# octacore.net
KiCad netlist of a schematic drawn in EAGLE
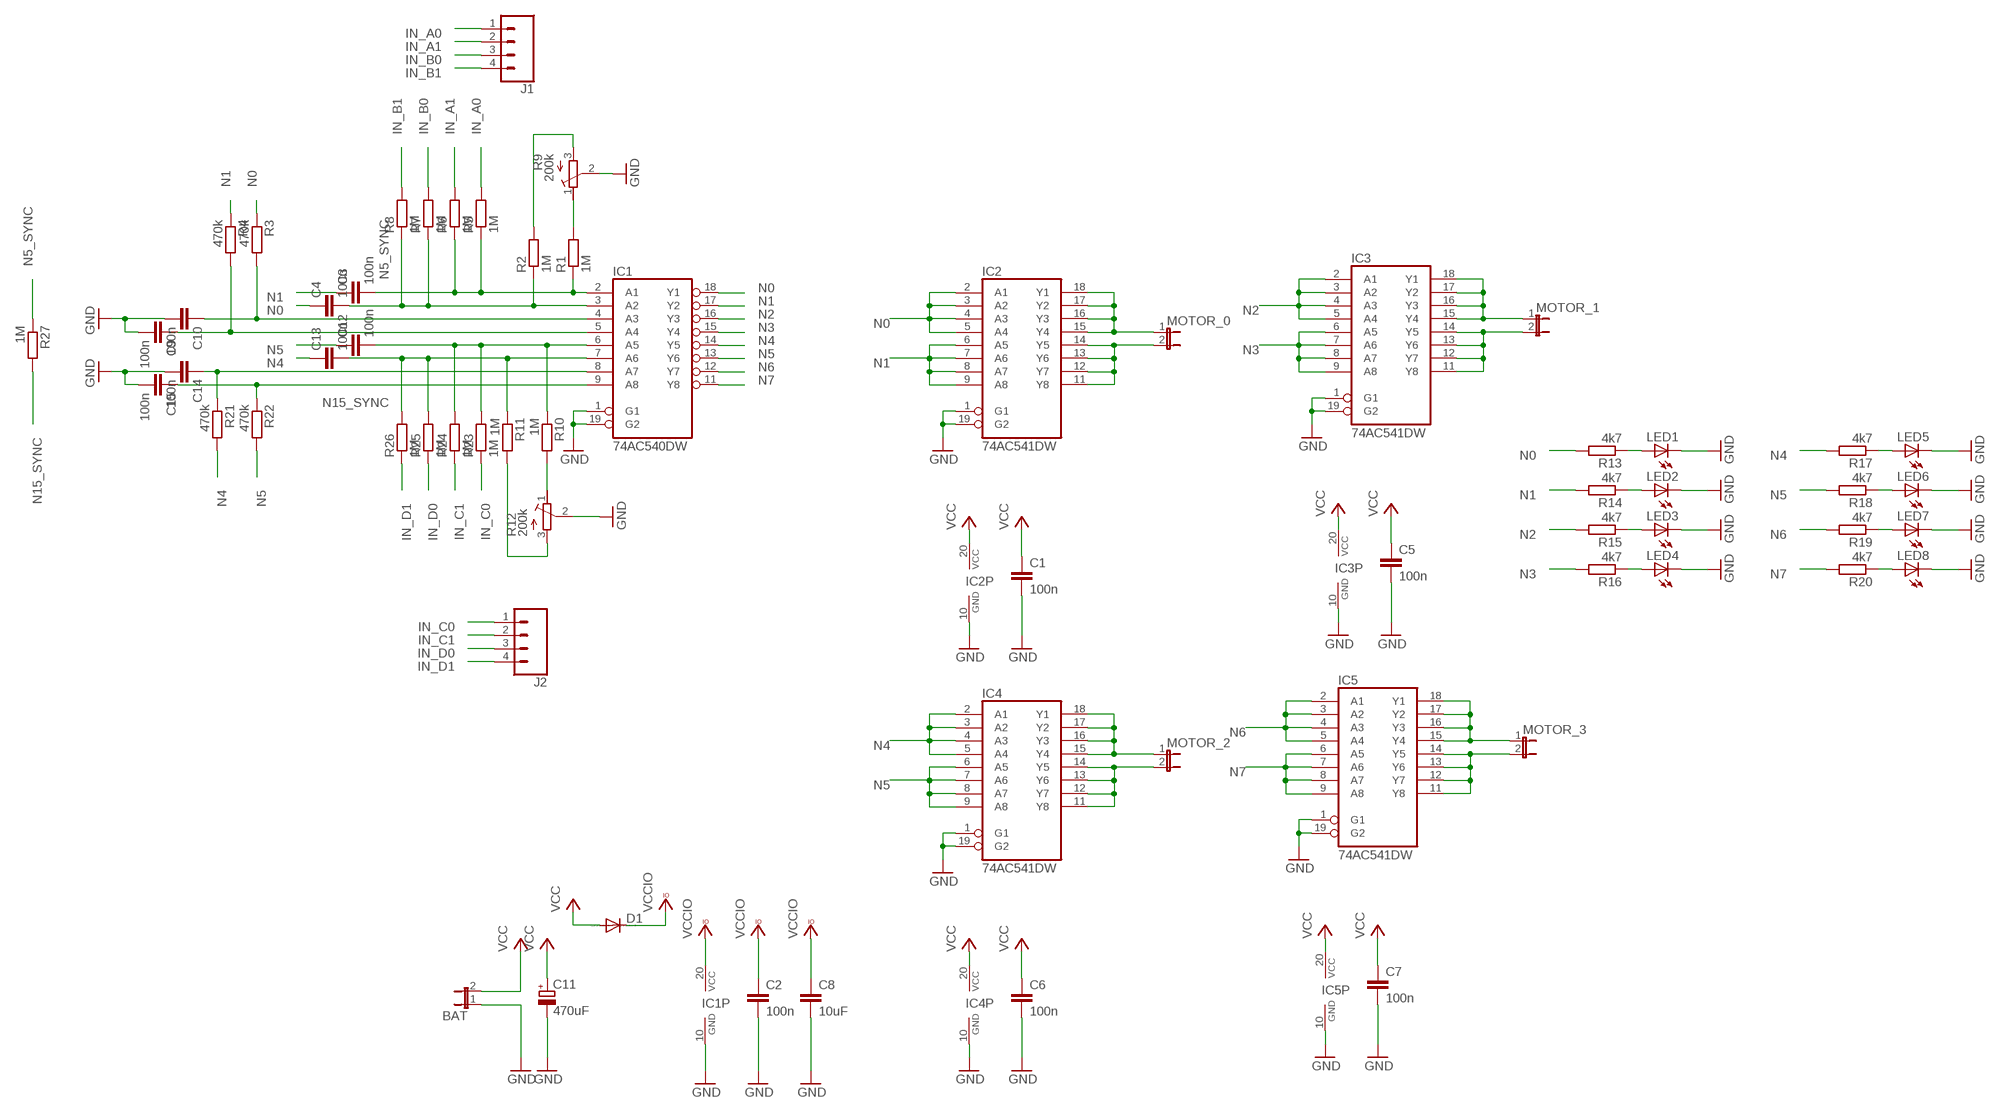
[diagram p0: schematic, sheet 1]

(export (version "E")
  (design (tool "Eeschema 10.0.6"))
  (components
    (comp (ref "BAT")
      (value "JUMPER_JP1E")
      (footprint "eagle-import:JUMPER_JP1")
      (libsource (lib "eagle-import") (part "JUMPER_JP1E"))
    )
    (comp (ref "C1")
      (value "100n")
      (footprint "eagle-import:C0805")
      (libsource (lib "eagle-import") (part "C-EUC0805"))
    )
    (comp (ref "C2")
      (value "100n")
      (footprint "eagle-import:C0805")
      (libsource (lib "eagle-import") (part "C-EUC0805"))
    )
    (comp (ref "C3")
      (value "100n")
      (footprint "eagle-import:C0805")
      (libsource (lib "eagle-import") (part "C-EUC0805"))
    )
    (comp (ref "C4")
      (value "100n")
      (footprint "eagle-import:C0805")
      (libsource (lib "eagle-import") (part "C-EUC0805"))
    )
    (comp (ref "C5")
      (value "100n")
      (footprint "eagle-import:C0805")
      (libsource (lib "eagle-import") (part "C-EUC0805"))
    )
    (comp (ref "C6")
      (value "100n")
      (footprint "eagle-import:C0805")
      (libsource (lib "eagle-import") (part "C-EUC0805"))
    )
    (comp (ref "C7")
      (value "100n")
      (footprint "eagle-import:C0805")
      (libsource (lib "eagle-import") (part "C-EUC0805"))
    )
    (comp (ref "C8")
      (value "10uF")
      (footprint "eagle-import:C0805")
      (libsource (lib "eagle-import") (part "C-EUC0805"))
    )
    (comp (ref "C9")
      (value "100n")
      (footprint "eagle-import:C0805")
      (libsource (lib "eagle-import") (part "C-EUC0805"))
    )
    (comp (ref "C10")
      (value "100n")
      (footprint "eagle-import:C0805")
      (libsource (lib "eagle-import") (part "C-EUC0805"))
    )
    (comp (ref "C11")
      (value "470uF")
      (footprint "eagle-import:140CLH-1010")
      (libsource (lib "eagle-import") (part "CPOL-EU140CLH-1010"))
    )
    (comp (ref "C12")
      (value "100n")
      (footprint "eagle-import:C0805")
      (libsource (lib "eagle-import") (part "C-EUC0805"))
    )
    (comp (ref "C13")
      (value "100n")
      (footprint "eagle-import:C0805")
      (libsource (lib "eagle-import") (part "C-EUC0805"))
    )
    (comp (ref "C14")
      (value "100n")
      (footprint "eagle-import:C0805")
      (libsource (lib "eagle-import") (part "C-EUC0805"))
    )
    (comp (ref "C15")
      (value "100n")
      (footprint "eagle-import:C0805")
      (libsource (lib "eagle-import") (part "C-EUC0805"))
    )
    (comp (ref "D1")
      (value "DIODE-DO214AA")
      (footprint "eagle-import:DO214AA")
      (libsource (lib "eagle-import") (part "DIODE-DO214AA"))
    )
    (comp (ref "IC1")
      (value "74AC540DW")
      (footprint "eagle-import:SO20W")
      (libsource (lib "eagle-import") (part "74540DWAC"))
    )
    (comp (ref "IC2")
      (value "74AC541DW")
      (footprint "eagle-import:SO20W")
      (libsource (lib "eagle-import") (part "74541DWAC"))
    )
    (comp (ref "IC3")
      (value "74AC541DW")
      (footprint "eagle-import:SO20W")
      (libsource (lib "eagle-import") (part "74541DWAC"))
    )
    (comp (ref "IC4")
      (value "74AC541DW")
      (footprint "eagle-import:SO20W")
      (libsource (lib "eagle-import") (part "74541DWAC"))
    )
    (comp (ref "IC5")
      (value "74AC541DW")
      (footprint "eagle-import:SO20W")
      (libsource (lib "eagle-import") (part "74541DWAC"))
    )
    (comp (ref "J1")
      (value "CONN_04")
      (footprint "eagle-import:1X04")
      (libsource (lib "eagle-import") (part "CONN_04"))
    )
    (comp (ref "J2")
      (value "CONN_04")
      (footprint "eagle-import:1X04")
      (libsource (lib "eagle-import") (part "CONN_04"))
    )
    (comp (ref "LED1")
      (value "LEDSML1206")
      (footprint "eagle-import:SML1206")
      (libsource (lib "eagle-import") (part "LEDSML1206"))
    )
    (comp (ref "LED2")
      (value "LEDSML1206")
      (footprint "eagle-import:SML1206")
      (libsource (lib "eagle-import") (part "LEDSML1206"))
    )
    (comp (ref "LED3")
      (value "LEDSML1206")
      (footprint "eagle-import:SML1206")
      (libsource (lib "eagle-import") (part "LEDSML1206"))
    )
    (comp (ref "LED4")
      (value "LEDSML1206")
      (footprint "eagle-import:SML1206")
      (libsource (lib "eagle-import") (part "LEDSML1206"))
    )
    (comp (ref "LED5")
      (value "LEDSML1206")
      (footprint "eagle-import:SML1206")
      (libsource (lib "eagle-import") (part "LEDSML1206"))
    )
    (comp (ref "LED6")
      (value "LEDSML1206")
      (footprint "eagle-import:SML1206")
      (libsource (lib "eagle-import") (part "LEDSML1206"))
    )
    (comp (ref "LED7")
      (value "LEDSML1206")
      (footprint "eagle-import:SML1206")
      (libsource (lib "eagle-import") (part "LEDSML1206"))
    )
    (comp (ref "LED8")
      (value "LEDSML1206")
      (footprint "eagle-import:SML1206")
      (libsource (lib "eagle-import") (part "LEDSML1206"))
    )
    (comp (ref "MOTOR_0")
      (value "JUMPER_JP1E")
      (footprint "eagle-import:JUMPER_JP1")
      (libsource (lib "eagle-import") (part "JUMPER_JP1E"))
    )
    (comp (ref "MOTOR_1")
      (value "JUMPER_JP1E")
      (footprint "eagle-import:JUMPER_JP1")
      (libsource (lib "eagle-import") (part "JUMPER_JP1E"))
    )
    (comp (ref "MOTOR_2")
      (value "JUMPER_JP1E")
      (footprint "eagle-import:JUMPER_JP1")
      (libsource (lib "eagle-import") (part "JUMPER_JP1E"))
    )
    (comp (ref "MOTOR_3")
      (value "JUMPER_JP1E")
      (footprint "eagle-import:JUMPER_JP1")
      (libsource (lib "eagle-import") (part "JUMPER_JP1E"))
    )
    (comp (ref "R1")
      (value "1M")
      (footprint "eagle-import:M0805")
      (libsource (lib "eagle-import") (part "R-EU_M0805"))
    )
    (comp (ref "R2")
      (value "1M")
      (footprint "eagle-import:M0805")
      (libsource (lib "eagle-import") (part "R-EU_M0805"))
    )
    (comp (ref "R3")
      (value "470k")
      (footprint "eagle-import:M0805")
      (libsource (lib "eagle-import") (part "R-EU_M0805"))
    )
    (comp (ref "R4")
      (value "470k")
      (footprint "eagle-import:M0805")
      (libsource (lib "eagle-import") (part "R-EU_M0805"))
    )
    (comp (ref "R5")
      (value "1M")
      (footprint "eagle-import:M0805")
      (libsource (lib "eagle-import") (part "R-EU_M0805"))
    )
    (comp (ref "R6")
      (value "1M")
      (footprint "eagle-import:M0805")
      (libsource (lib "eagle-import") (part "R-EU_M0805"))
    )
    (comp (ref "R7")
      (value "1M")
      (footprint "eagle-import:M0805")
      (libsource (lib "eagle-import") (part "R-EU_M0805"))
    )
    (comp (ref "R8")
      (value "1M")
      (footprint "eagle-import:M0805")
      (libsource (lib "eagle-import") (part "R-EU_M0805"))
    )
    (comp (ref "R9")
      (value "200k")
      (footprint "eagle-import:RTRIM3314G")
      (libsource (lib "eagle-import") (part "R-TRIMM3314G"))
    )
    (comp (ref "R10")
      (value "1M")
      (footprint "eagle-import:M0805")
      (libsource (lib "eagle-import") (part "R-EU_M0805"))
    )
    (comp (ref "R11")
      (value "1M")
      (footprint "eagle-import:M0805")
      (libsource (lib "eagle-import") (part "R-EU_M0805"))
    )
    (comp (ref "R12")
      (value "200k")
      (footprint "eagle-import:RTRIM3314G")
      (libsource (lib "eagle-import") (part "R-TRIMM3314G"))
    )
    (comp (ref "R13")
      (value "4k7")
      (footprint "eagle-import:M0805")
      (libsource (lib "eagle-import") (part "R-EU_M0805"))
    )
    (comp (ref "R14")
      (value "4k7")
      (footprint "eagle-import:M0805")
      (libsource (lib "eagle-import") (part "R-EU_M0805"))
    )
    (comp (ref "R15")
      (value "4k7")
      (footprint "eagle-import:M0805")
      (libsource (lib "eagle-import") (part "R-EU_M0805"))
    )
    (comp (ref "R16")
      (value "4k7")
      (footprint "eagle-import:M0805")
      (libsource (lib "eagle-import") (part "R-EU_M0805"))
    )
    (comp (ref "R17")
      (value "4k7")
      (footprint "eagle-import:M0805")
      (libsource (lib "eagle-import") (part "R-EU_M0805"))
    )
    (comp (ref "R18")
      (value "4k7")
      (footprint "eagle-import:M0805")
      (libsource (lib "eagle-import") (part "R-EU_M0805"))
    )
    (comp (ref "R19")
      (value "4k7")
      (footprint "eagle-import:M0805")
      (libsource (lib "eagle-import") (part "R-EU_M0805"))
    )
    (comp (ref "R20")
      (value "4k7")
      (footprint "eagle-import:M0805")
      (libsource (lib "eagle-import") (part "R-EU_M0805"))
    )
    (comp (ref "R21")
      (value "470k")
      (footprint "eagle-import:M0805")
      (libsource (lib "eagle-import") (part "R-EU_M0805"))
    )
    (comp (ref "R22")
      (value "470k")
      (footprint "eagle-import:M0805")
      (libsource (lib "eagle-import") (part "R-EU_M0805"))
    )
    (comp (ref "R23")
      (value "1M")
      (footprint "eagle-import:M0805")
      (libsource (lib "eagle-import") (part "R-EU_M0805"))
    )
    (comp (ref "R24")
      (value "1M")
      (footprint "eagle-import:M0805")
      (libsource (lib "eagle-import") (part "R-EU_M0805"))
    )
    (comp (ref "R25")
      (value "1M")
      (footprint "eagle-import:M0805")
      (libsource (lib "eagle-import") (part "R-EU_M0805"))
    )
    (comp (ref "R26")
      (value "1M")
      (footprint "eagle-import:M0805")
      (libsource (lib "eagle-import") (part "R-EU_M0805"))
    )
    (comp (ref "R27")
      (value "1M")
      (footprint "eagle-import:M0805")
      (libsource (lib "eagle-import") (part "R-EU_M0805"))
    )
  )
  (nets
    (net (code "1") (name "/IN_A0") (class "Default")
      (node (ref "J1") (pin "1") (pinfunction "1_1") (pintype "passive"))
      (node (ref "R5") (pin "2") (pinfunction "2_2") (pintype "passive"))
    )
    (net (code "2") (name "/IN_A1") (class "Default")
      (node (ref "J1") (pin "2") (pinfunction "2_2") (pintype "passive"))
      (node (ref "R6") (pin "2") (pinfunction "2_2") (pintype "passive"))
    )
    (net (code "3") (name "/IN_B0") (class "Default")
      (node (ref "J1") (pin "3") (pinfunction "3_3") (pintype "passive"))
      (node (ref "R7") (pin "2") (pinfunction "2_2") (pintype "passive"))
    )
    (net (code "4") (name "/IN_B1") (class "Default")
      (node (ref "J1") (pin "4") (pinfunction "4_4") (pintype "passive"))
      (node (ref "R8") (pin "2") (pinfunction "2_2") (pintype "passive"))
    )
    (net (code "5") (name "/IN_C0") (class "Default")
      (node (ref "J2") (pin "1") (pinfunction "1_1") (pintype "passive"))
      (node (ref "R23") (pin "1") (pinfunction "1_1") (pintype "passive"))
    )
    (net (code "6") (name "/IN_C1") (class "Default")
      (node (ref "J2") (pin "2") (pinfunction "2_2") (pintype "passive"))
      (node (ref "R24") (pin "1") (pinfunction "1_1") (pintype "passive"))
    )
    (net (code "7") (name "/IN_D0") (class "Default")
      (node (ref "J2") (pin "3") (pinfunction "3_3") (pintype "passive"))
      (node (ref "R25") (pin "1") (pinfunction "1_1") (pintype "passive"))
    )
    (net (code "8") (name "/IN_D1") (class "Default")
      (node (ref "J2") (pin "4") (pinfunction "4_4") (pintype "passive"))
      (node (ref "R26") (pin "1") (pinfunction "1_1") (pintype "passive"))
    )
    (net (code "9") (name "/N0") (class "Default")
      (node (ref "C4") (pin "1") (pinfunction "1_1") (pintype "passive"))
      (node (ref "IC1") (pin "18") (pinfunction "Y1_18") (pintype "tri_state"))
      (node (ref "IC2") (pin "2") (pinfunction "A1_2") (pintype "input"))
      (node (ref "IC2") (pin "3") (pinfunction "A2_3") (pintype "input"))
      (node (ref "IC2") (pin "4") (pinfunction "A3_4") (pintype "input"))
      (node (ref "IC2") (pin "5") (pinfunction "A4_5") (pintype "input"))
      (node (ref "R13") (pin "2") (pinfunction "2_2") (pintype "passive"))
      (node (ref "R3") (pin "1") (pinfunction "1_1") (pintype "passive"))
    )
    (net (code "10") (name "/N1") (class "Default")
      (node (ref "C3") (pin "1") (pinfunction "1_1") (pintype "passive"))
      (node (ref "IC1") (pin "17") (pinfunction "Y2_17") (pintype "tri_state"))
      (node (ref "IC2") (pin "6") (pinfunction "A5_6") (pintype "input"))
      (node (ref "IC2") (pin "7") (pinfunction "A6_7") (pintype "input"))
      (node (ref "IC2") (pin "8") (pinfunction "A7_8") (pintype "input"))
      (node (ref "IC2") (pin "9") (pinfunction "A8_9") (pintype "input"))
      (node (ref "R14") (pin "2") (pinfunction "2_2") (pintype "passive"))
      (node (ref "R4") (pin "1") (pinfunction "1_1") (pintype "passive"))
    )
    (net (code "11") (name "/N2") (class "Default")
      (node (ref "IC1") (pin "16") (pinfunction "Y3_16") (pintype "tri_state"))
      (node (ref "IC3") (pin "2") (pinfunction "A1_2") (pintype "input"))
      (node (ref "IC3") (pin "3") (pinfunction "A2_3") (pintype "input"))
      (node (ref "IC3") (pin "4") (pinfunction "A3_4") (pintype "input"))
      (node (ref "IC3") (pin "5") (pinfunction "A4_5") (pintype "input"))
      (node (ref "R15") (pin "2") (pinfunction "2_2") (pintype "passive"))
    )
    (net (code "12") (name "/N3") (class "Default")
      (node (ref "IC1") (pin "15") (pinfunction "Y4_15") (pintype "tri_state"))
      (node (ref "IC3") (pin "6") (pinfunction "A5_6") (pintype "input"))
      (node (ref "IC3") (pin "7") (pinfunction "A6_7") (pintype "input"))
      (node (ref "IC3") (pin "8") (pinfunction "A7_8") (pintype "input"))
      (node (ref "IC3") (pin "9") (pinfunction "A8_9") (pintype "input"))
      (node (ref "R16") (pin "2") (pinfunction "2_2") (pintype "passive"))
    )
    (net (code "13") (name "/N4") (class "Default")
      (node (ref "C13") (pin "1") (pinfunction "1_1") (pintype "passive"))
      (node (ref "IC1") (pin "14") (pinfunction "Y5_14") (pintype "tri_state"))
      (node (ref "IC4") (pin "2") (pinfunction "A1_2") (pintype "input"))
      (node (ref "IC4") (pin "3") (pinfunction "A2_3") (pintype "input"))
      (node (ref "IC4") (pin "4") (pinfunction "A3_4") (pintype "input"))
      (node (ref "IC4") (pin "5") (pinfunction "A4_5") (pintype "input"))
      (node (ref "R17") (pin "2") (pinfunction "2_2") (pintype "passive"))
      (node (ref "R21") (pin "2") (pinfunction "2_2") (pintype "passive"))
    )
    (net (code "14") (name "/N5") (class "Default")
      (node (ref "C12") (pin "1") (pinfunction "1_1") (pintype "passive"))
      (node (ref "IC1") (pin "13") (pinfunction "Y6_13") (pintype "tri_state"))
      (node (ref "IC4") (pin "6") (pinfunction "A5_6") (pintype "input"))
      (node (ref "IC4") (pin "7") (pinfunction "A6_7") (pintype "input"))
      (node (ref "IC4") (pin "8") (pinfunction "A7_8") (pintype "input"))
      (node (ref "IC4") (pin "9") (pinfunction "A8_9") (pintype "input"))
      (node (ref "R18") (pin "2") (pinfunction "2_2") (pintype "passive"))
      (node (ref "R22") (pin "2") (pinfunction "2_2") (pintype "passive"))
    )
    (net (code "15") (name "/N5_SYNC") (class "Default")
      (node (ref "C3") (pin "2") (pinfunction "2_2") (pintype "passive"))
      (node (ref "IC1") (pin "2") (pinfunction "A1_2") (pintype "input"))
      (node (ref "R1") (pin "1") (pinfunction "1_1") (pintype "passive"))
      (node (ref "R27") (pin "1") (pinfunction "1_1") (pintype "passive"))
      (node (ref "R5") (pin "1") (pinfunction "1_1") (pintype "passive"))
      (node (ref "R6") (pin "1") (pinfunction "1_1") (pintype "passive"))
    )
    (net (code "16") (name "/N6") (class "Default")
      (node (ref "IC1") (pin "12") (pinfunction "Y7_12") (pintype "tri_state"))
      (node (ref "IC5") (pin "2") (pinfunction "A1_2") (pintype "input"))
      (node (ref "IC5") (pin "3") (pinfunction "A2_3") (pintype "input"))
      (node (ref "IC5") (pin "4") (pinfunction "A3_4") (pintype "input"))
      (node (ref "IC5") (pin "5") (pinfunction "A4_5") (pintype "input"))
      (node (ref "R19") (pin "2") (pinfunction "2_2") (pintype "passive"))
    )
    (net (code "17") (name "/N7") (class "Default")
      (node (ref "IC1") (pin "11") (pinfunction "Y8_11") (pintype "tri_state"))
      (node (ref "IC5") (pin "6") (pinfunction "A5_6") (pintype "input"))
      (node (ref "IC5") (pin "7") (pinfunction "A6_7") (pintype "input"))
      (node (ref "IC5") (pin "8") (pinfunction "A7_8") (pintype "input"))
      (node (ref "IC5") (pin "9") (pinfunction "A8_9") (pintype "input"))
      (node (ref "R20") (pin "2") (pinfunction "2_2") (pintype "passive"))
    )
    (net (code "18") (name "/N15_SYNC") (class "Default")
      (node (ref "C12") (pin "2") (pinfunction "2_2") (pintype "passive"))
      (node (ref "IC1") (pin "6") (pinfunction "A5_6") (pintype "input"))
      (node (ref "R10") (pin "1") (pinfunction "1_1") (pintype "passive"))
      (node (ref "R23") (pin "2") (pinfunction "2_2") (pintype "passive"))
      (node (ref "R24") (pin "2") (pinfunction "2_2") (pintype "passive"))
      (node (ref "R27") (pin "2") (pinfunction "2_2") (pintype "passive"))
    )
    (net (code "19") (name "GND") (class "Default")
      (node (ref "BAT") (pin "1") (pinfunction "1_1") (pintype "passive"))
      (node (ref "C1") (pin "2") (pinfunction "2_2") (pintype "passive"))
      (node (ref "C10") (pin "2") (pinfunction "2_2") (pintype "passive"))
      (node (ref "C11") (pin "-") (pinfunction "-_-") (pintype "passive"))
      (node (ref "C14") (pin "2") (pinfunction "2_2") (pintype "passive"))
      (node (ref "C15") (pin "2") (pinfunction "2_2") (pintype "passive"))
      (node (ref "C2") (pin "2") (pinfunction "2_2") (pintype "passive"))
      (node (ref "C5") (pin "2") (pinfunction "2_2") (pintype "passive"))
      (node (ref "C6") (pin "2") (pinfunction "2_2") (pintype "passive"))
      (node (ref "C7") (pin "2") (pinfunction "2_2") (pintype "passive"))
      (node (ref "C8") (pin "2") (pinfunction "2_2") (pintype "passive"))
      (node (ref "C9") (pin "2") (pinfunction "2_2") (pintype "passive"))
      (node (ref "IC1") (pin "1") (pinfunction "G1_1") (pintype "input"))
      (node (ref "IC1") (pin "10") (pinfunction "GND_10") (pintype "power_in"))
      (node (ref "IC1") (pin "19") (pinfunction "G2_19") (pintype "input"))
      (node (ref "IC2") (pin "1") (pinfunction "G1_1") (pintype "input"))
      (node (ref "IC2") (pin "10") (pinfunction "GND_10") (pintype "power_in"))
      (node (ref "IC2") (pin "19") (pinfunction "G2_19") (pintype "input"))
      (node (ref "IC3") (pin "1") (pinfunction "G1_1") (pintype "input"))
      (node (ref "IC3") (pin "10") (pinfunction "GND_10") (pintype "power_in"))
      (node (ref "IC3") (pin "19") (pinfunction "G2_19") (pintype "input"))
      (node (ref "IC4") (pin "1") (pinfunction "G1_1") (pintype "input"))
      (node (ref "IC4") (pin "10") (pinfunction "GND_10") (pintype "power_in"))
      (node (ref "IC4") (pin "19") (pinfunction "G2_19") (pintype "input"))
      (node (ref "IC5") (pin "1") (pinfunction "G1_1") (pintype "input"))
      (node (ref "IC5") (pin "10") (pinfunction "GND_10") (pintype "power_in"))
      (node (ref "IC5") (pin "19") (pinfunction "G2_19") (pintype "input"))
      (node (ref "LED1") (pin "C") (pinfunction "C_C") (pintype "passive"))
      (node (ref "LED2") (pin "C") (pinfunction "C_C") (pintype "passive"))
      (node (ref "LED3") (pin "C") (pinfunction "C_C") (pintype "passive"))
      (node (ref "LED4") (pin "C") (pinfunction "C_C") (pintype "passive"))
      (node (ref "LED5") (pin "C") (pinfunction "C_C") (pintype "passive"))
      (node (ref "LED6") (pin "C") (pinfunction "C_C") (pintype "passive"))
      (node (ref "LED7") (pin "C") (pinfunction "C_C") (pintype "passive"))
      (node (ref "LED8") (pin "C") (pinfunction "C_C") (pintype "passive"))
      (node (ref "R12") (pin "2") (pinfunction "S_2") (pintype "passive"))
      (node (ref "R9") (pin "2") (pinfunction "S_2") (pintype "passive"))
    )
    (net (code "20") (name "Net-(IC1A-A2)") (class "Default")
      (node (ref "C4") (pin "2") (pinfunction "2_2") (pintype "passive"))
      (node (ref "IC1") (pin "3") (pinfunction "A2_3") (pintype "input"))
      (node (ref "R2") (pin "1") (pinfunction "1_1") (pintype "passive"))
      (node (ref "R7") (pin "1") (pinfunction "1_1") (pintype "passive"))
      (node (ref "R8") (pin "1") (pinfunction "1_1") (pintype "passive"))
    )
    (net (code "21") (name "Net-(IC1A-A3)") (class "Default")
      (node (ref "C10") (pin "1") (pinfunction "1_1") (pintype "passive"))
      (node (ref "IC1") (pin "4") (pinfunction "A3_4") (pintype "input"))
      (node (ref "R3") (pin "2") (pinfunction "2_2") (pintype "passive"))
    )
    (net (code "22") (name "Net-(IC1A-A4)") (class "Default")
      (node (ref "C9") (pin "1") (pinfunction "1_1") (pintype "passive"))
      (node (ref "IC1") (pin "5") (pinfunction "A4_5") (pintype "input"))
      (node (ref "R4") (pin "2") (pinfunction "2_2") (pintype "passive"))
    )
    (net (code "23") (name "Net-(IC1A-A6)") (class "Default")
      (node (ref "C13") (pin "2") (pinfunction "2_2") (pintype "passive"))
      (node (ref "IC1") (pin "7") (pinfunction "A6_7") (pintype "input"))
      (node (ref "R11") (pin "1") (pinfunction "1_1") (pintype "passive"))
      (node (ref "R25") (pin "2") (pinfunction "2_2") (pintype "passive"))
      (node (ref "R26") (pin "2") (pinfunction "2_2") (pintype "passive"))
    )
    (net (code "24") (name "Net-(IC1A-A7)") (class "Default")
      (node (ref "C14") (pin "1") (pinfunction "1_1") (pintype "passive"))
      (node (ref "IC1") (pin "8") (pinfunction "A7_8") (pintype "input"))
      (node (ref "R21") (pin "1") (pinfunction "1_1") (pintype "passive"))
    )
    (net (code "25") (name "Net-(IC1A-A8)") (class "Default")
      (node (ref "C15") (pin "1") (pinfunction "1_1") (pintype "passive"))
      (node (ref "IC1") (pin "9") (pinfunction "A8_9") (pintype "input"))
      (node (ref "R22") (pin "1") (pinfunction "1_1") (pintype "passive"))
    )
    (net (code "26") (name "Net-(IC2A-Y1)") (class "Default")
      (node (ref "IC2") (pin "15") (pinfunction "Y4_15") (pintype "tri_state"))
      (node (ref "IC2") (pin "16") (pinfunction "Y3_16") (pintype "tri_state"))
      (node (ref "IC2") (pin "17") (pinfunction "Y2_17") (pintype "tri_state"))
      (node (ref "IC2") (pin "18") (pinfunction "Y1_18") (pintype "tri_state"))
      (node (ref "MOTOR_0") (pin "1") (pinfunction "1_1") (pintype "passive"))
    )
    (net (code "27") (name "Net-(IC2A-Y5)") (class "Default")
      (node (ref "IC2") (pin "11") (pinfunction "Y8_11") (pintype "tri_state"))
      (node (ref "IC2") (pin "12") (pinfunction "Y7_12") (pintype "tri_state"))
      (node (ref "IC2") (pin "13") (pinfunction "Y6_13") (pintype "tri_state"))
      (node (ref "IC2") (pin "14") (pinfunction "Y5_14") (pintype "tri_state"))
      (node (ref "MOTOR_0") (pin "2") (pinfunction "2_2") (pintype "passive"))
    )
    (net (code "28") (name "Net-(IC3A-Y1)") (class "Default")
      (node (ref "IC3") (pin "15") (pinfunction "Y4_15") (pintype "tri_state"))
      (node (ref "IC3") (pin "16") (pinfunction "Y3_16") (pintype "tri_state"))
      (node (ref "IC3") (pin "17") (pinfunction "Y2_17") (pintype "tri_state"))
      (node (ref "IC3") (pin "18") (pinfunction "Y1_18") (pintype "tri_state"))
      (node (ref "MOTOR_1") (pin "1") (pinfunction "1_1") (pintype "passive"))
    )
    (net (code "29") (name "Net-(IC3A-Y5)") (class "Default")
      (node (ref "IC3") (pin "11") (pinfunction "Y8_11") (pintype "tri_state"))
      (node (ref "IC3") (pin "12") (pinfunction "Y7_12") (pintype "tri_state"))
      (node (ref "IC3") (pin "13") (pinfunction "Y6_13") (pintype "tri_state"))
      (node (ref "IC3") (pin "14") (pinfunction "Y5_14") (pintype "tri_state"))
      (node (ref "MOTOR_1") (pin "2") (pinfunction "2_2") (pintype "passive"))
    )
    (net (code "30") (name "Net-(IC4A-Y1)") (class "Default")
      (node (ref "IC4") (pin "15") (pinfunction "Y4_15") (pintype "tri_state"))
      (node (ref "IC4") (pin "16") (pinfunction "Y3_16") (pintype "tri_state"))
      (node (ref "IC4") (pin "17") (pinfunction "Y2_17") (pintype "tri_state"))
      (node (ref "IC4") (pin "18") (pinfunction "Y1_18") (pintype "tri_state"))
      (node (ref "MOTOR_2") (pin "1") (pinfunction "1_1") (pintype "passive"))
    )
    (net (code "31") (name "Net-(IC4A-Y5)") (class "Default")
      (node (ref "IC4") (pin "11") (pinfunction "Y8_11") (pintype "tri_state"))
      (node (ref "IC4") (pin "12") (pinfunction "Y7_12") (pintype "tri_state"))
      (node (ref "IC4") (pin "13") (pinfunction "Y6_13") (pintype "tri_state"))
      (node (ref "IC4") (pin "14") (pinfunction "Y5_14") (pintype "tri_state"))
      (node (ref "MOTOR_2") (pin "2") (pinfunction "2_2") (pintype "passive"))
    )
    (net (code "32") (name "Net-(IC5A-Y1)") (class "Default")
      (node (ref "IC5") (pin "15") (pinfunction "Y4_15") (pintype "tri_state"))
      (node (ref "IC5") (pin "16") (pinfunction "Y3_16") (pintype "tri_state"))
      (node (ref "IC5") (pin "17") (pinfunction "Y2_17") (pintype "tri_state"))
      (node (ref "IC5") (pin "18") (pinfunction "Y1_18") (pintype "tri_state"))
      (node (ref "MOTOR_3") (pin "1") (pinfunction "1_1") (pintype "passive"))
    )
    (net (code "33") (name "Net-(IC5A-Y5)") (class "Default")
      (node (ref "IC5") (pin "11") (pinfunction "Y8_11") (pintype "tri_state"))
      (node (ref "IC5") (pin "12") (pinfunction "Y7_12") (pintype "tri_state"))
      (node (ref "IC5") (pin "13") (pinfunction "Y6_13") (pintype "tri_state"))
      (node (ref "IC5") (pin "14") (pinfunction "Y5_14") (pintype "tri_state"))
      (node (ref "MOTOR_3") (pin "2") (pinfunction "2_2") (pintype "passive"))
    )
    (net (code "34") (name "Net-(LED1-PadA)") (class "Default")
      (node (ref "LED1") (pin "A") (pinfunction "A_A") (pintype "passive"))
      (node (ref "R13") (pin "1") (pinfunction "1_1") (pintype "passive"))
    )
    (net (code "35") (name "Net-(LED2-PadA)") (class "Default")
      (node (ref "LED2") (pin "A") (pinfunction "A_A") (pintype "passive"))
      (node (ref "R14") (pin "1") (pinfunction "1_1") (pintype "passive"))
    )
    (net (code "36") (name "Net-(LED3-PadA)") (class "Default")
      (node (ref "LED3") (pin "A") (pinfunction "A_A") (pintype "passive"))
      (node (ref "R15") (pin "1") (pinfunction "1_1") (pintype "passive"))
    )
    (net (code "37") (name "Net-(LED4-PadA)") (class "Default")
      (node (ref "LED4") (pin "A") (pinfunction "A_A") (pintype "passive"))
      (node (ref "R16") (pin "1") (pinfunction "1_1") (pintype "passive"))
    )
    (net (code "38") (name "Net-(LED5-PadA)") (class "Default")
      (node (ref "LED5") (pin "A") (pinfunction "A_A") (pintype "passive"))
      (node (ref "R17") (pin "1") (pinfunction "1_1") (pintype "passive"))
    )
    (net (code "39") (name "Net-(LED6-PadA)") (class "Default")
      (node (ref "LED6") (pin "A") (pinfunction "A_A") (pintype "passive"))
      (node (ref "R18") (pin "1") (pinfunction "1_1") (pintype "passive"))
    )
    (net (code "40") (name "Net-(LED7-PadA)") (class "Default")
      (node (ref "LED7") (pin "A") (pinfunction "A_A") (pintype "passive"))
      (node (ref "R19") (pin "1") (pinfunction "1_1") (pintype "passive"))
    )
    (net (code "41") (name "Net-(LED8-PadA)") (class "Default")
      (node (ref "LED8") (pin "A") (pinfunction "A_A") (pintype "passive"))
      (node (ref "R20") (pin "1") (pinfunction "1_1") (pintype "passive"))
    )
    (net (code "42") (name "Net-(R9-A)") (class "Default")
      (node (ref "R2") (pin "2") (pinfunction "2_2") (pintype "passive"))
      (node (ref "R9") (pin "3") (pinfunction "A_3") (pintype "passive"))
    )
    (net (code "43") (name "Net-(R9-E)") (class "Default")
      (node (ref "R1") (pin "2") (pinfunction "2_2") (pintype "passive"))
      (node (ref "R9") (pin "1") (pinfunction "E_1") (pintype "passive"))
    )
    (net (code "44") (name "Net-(R12-A)") (class "Default")
      (node (ref "R11") (pin "2") (pinfunction "2_2") (pintype "passive"))
      (node (ref "R12") (pin "3") (pinfunction "A_3") (pintype "passive"))
    )
    (net (code "45") (name "Net-(R12-E)") (class "Default")
      (node (ref "R10") (pin "2") (pinfunction "2_2") (pintype "passive"))
      (node (ref "R12") (pin "1") (pinfunction "E_1") (pintype "passive"))
    )
    (net (code "46") (name "VCC") (class "Default")
      (node (ref "BAT") (pin "2") (pinfunction "2_2") (pintype "passive"))
      (node (ref "C1") (pin "1") (pinfunction "1_1") (pintype "passive"))
      (node (ref "C11") (pin "+") (pinfunction "+_+") (pintype "passive"))
      (node (ref "C5") (pin "1") (pinfunction "1_1") (pintype "passive"))
      (node (ref "C6") (pin "1") (pinfunction "1_1") (pintype "passive"))
      (node (ref "C7") (pin "1") (pinfunction "1_1") (pintype "passive"))
      (node (ref "D1") (pin "A") (pinfunction "A_A") (pintype "passive"))
      (node (ref "IC2") (pin "20") (pinfunction "VCC_20") (pintype "power_in"))
      (node (ref "IC3") (pin "20") (pinfunction "VCC_20") (pintype "power_in"))
      (node (ref "IC4") (pin "20") (pinfunction "VCC_20") (pintype "power_in"))
      (node (ref "IC5") (pin "20") (pinfunction "VCC_20") (pintype "power_in"))
    )
    (net (code "47") (name "VCCIO") (class "Default")
      (node (ref "C2") (pin "1") (pinfunction "1_1") (pintype "passive"))
      (node (ref "C8") (pin "1") (pinfunction "1_1") (pintype "passive"))
      (node (ref "D1") (pin "C") (pinfunction "C_C") (pintype "passive"))
      (node (ref "IC1") (pin "20") (pinfunction "VCC_20") (pintype "power_in"))
    )
  )
)
